# 5_Airframe-NXP_i_MX7_Power.net
KiCad netlist of a schematic drawn in Altium Designer
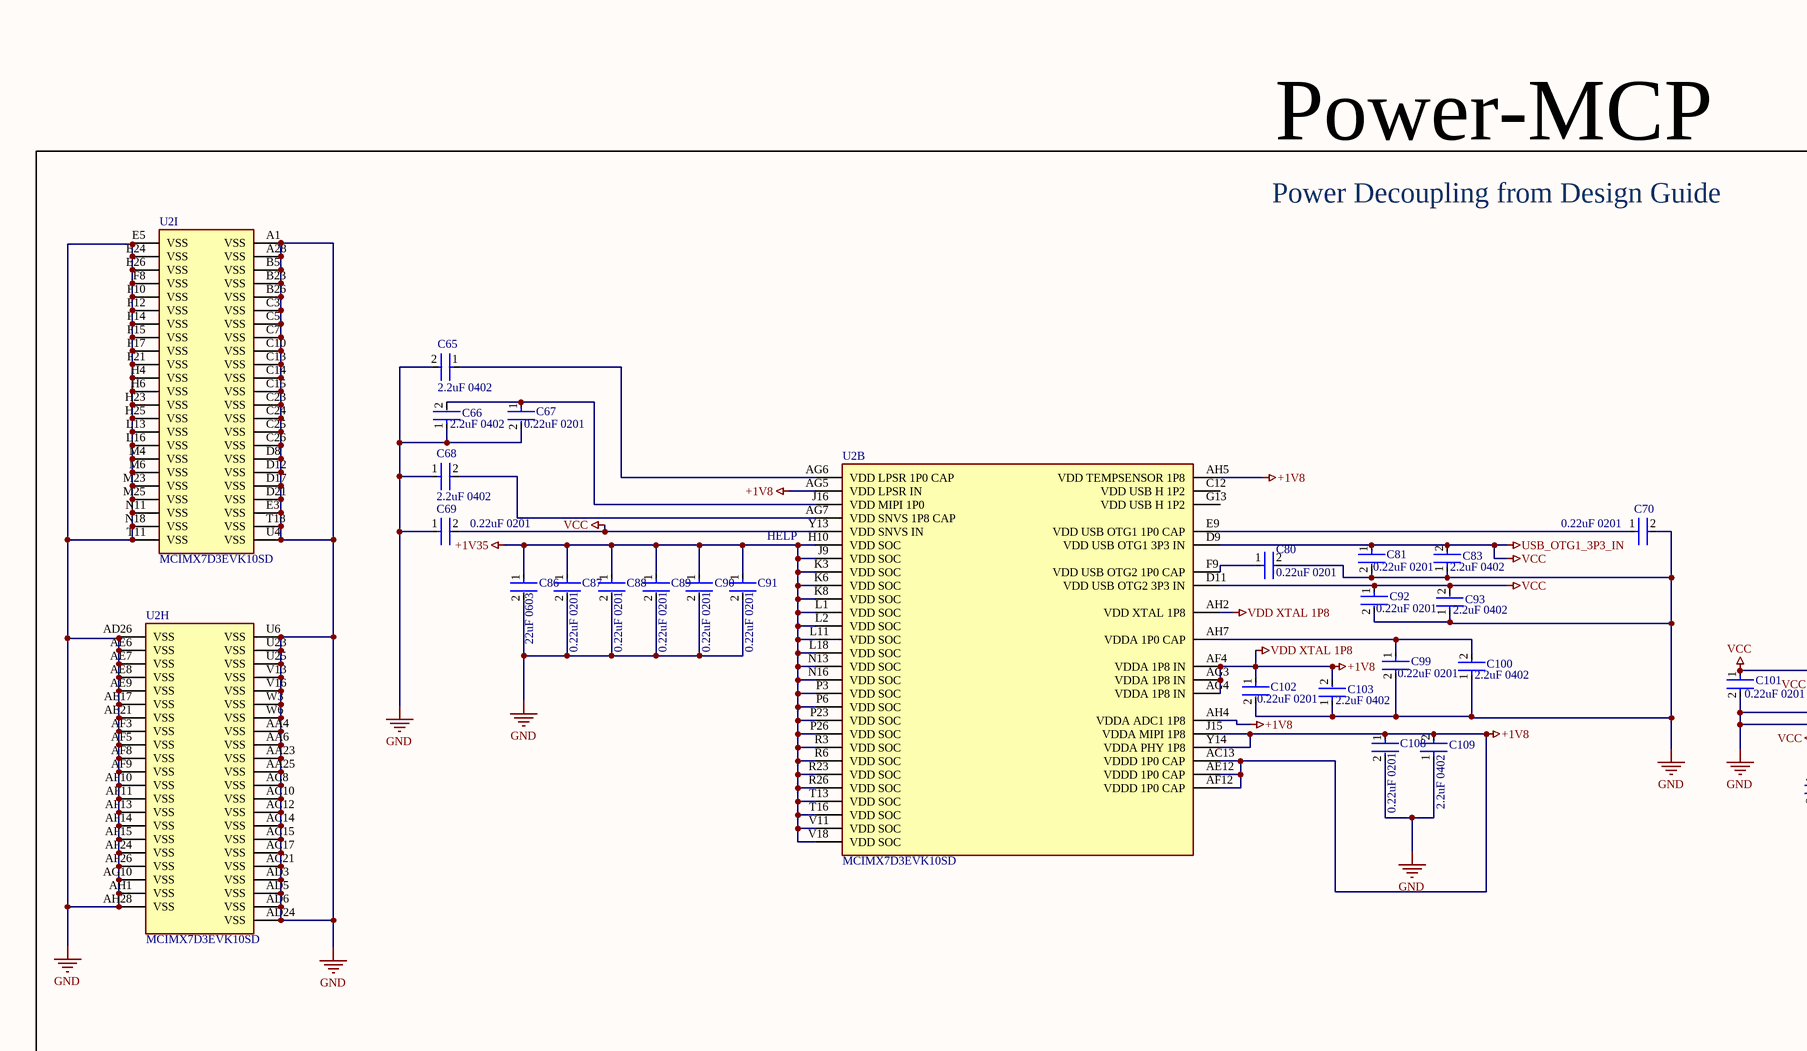
[diagram p0: 5_Airframe-NXP_i.MX7_Power.SchDoc, left]
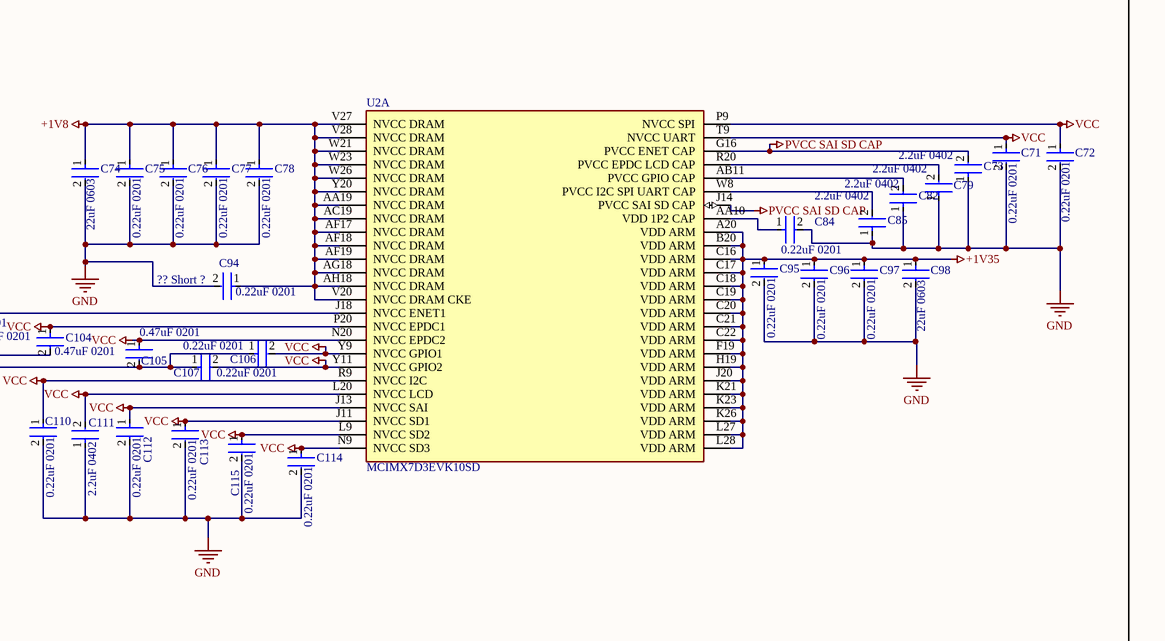
[diagram p1: 5_Airframe-NXP_i.MX7_Power.SchDoc, right]

(export (version "E")
  (design (tool "Eeschema 10.0.6"))
  (components
    (comp (ref "C65")
      (value "2.2uF 0402")
      (footprint "FP-C0402C225M9PACTU-MFG")
      (description "CAP CER 2.2UF 6.3V X5R 0402")
      (fields (field (name "VOLTAGE") "6.3V") (field (name "TOLERANCE") "20%"))
      (libsource (lib "Altium Content Vault") (part "b4654b650e69147ec39a6b967a45e02"))
    )
    (comp (ref "C66")
      (value "2.2uF 0402")
      (footprint "FP-C0402C225M9PACTU-MFG")
      (description "CAP CER 2.2UF 6.3V X5R 0402")
      (fields (field (name "VOLTAGE") "6.3V") (field (name "TOLERANCE") "20%"))
      (libsource (lib "Altium Content Vault") (part "b4654b650e69147ec39a6b967a45e02"))
    )
    (comp (ref "C67")
      (value "0.22uF 0201")
      (footprint "FP-C0603-030-0_03-IPC_C")
      (description "Multilayer Ceramic Capacitors 220nF ±10% 6.3V X6S SMD 0201")
      (fields (field (name "TOLERANCE") "10%"))
      (libsource (lib "Altium Content Vault") (part "02cd4be3c70576c341d710602a673aa"))
    )
    (comp (ref "C68")
      (value "2.2uF 0402")
      (footprint "FP-C0402C225M9PACTU-MFG")
      (description "CAP CER 2.2UF 6.3V X5R 0402")
      (fields (field (name "VOLTAGE") "6.3V") (field (name "TOLERANCE") "20%"))
      (libsource (lib "Altium Content Vault") (part "b4654b650e69147ec39a6b967a45e02"))
    )
    (comp (ref "C69")
      (value "0.22uF 0201")
      (footprint "FP-C0603-030-0_03-IPC_C")
      (description "Multilayer Ceramic Capacitors 220nF ±10% 6.3V X6S SMD 0201")
      (fields (field (name "TOLERANCE") "10%"))
      (libsource (lib "Altium Content Vault") (part "02cd4be3c70576c341d710602a673aa"))
    )
    (comp (ref "C70")
      (value "0.22uF 0201")
      (footprint "FP-C0603-030-0_03-IPC_C")
      (description "Multilayer Ceramic Capacitors 220nF ±10% 6.3V X6S SMD 0201")
      (fields (field (name "TOLERANCE") "10%"))
      (libsource (lib "Altium Content Vault") (part "02cd4be3c70576c341d710602a673aa"))
    )
    (comp (ref "C71")
      (value "0.22uF 0201")
      (footprint "FP-C0603-030-0_03-IPC_C")
      (description "Multilayer Ceramic Capacitors 220nF ±10% 6.3V X6S SMD 0201")
      (fields (field (name "TOLERANCE") "10%"))
      (libsource (lib "Altium Content Vault") (part "02cd4be3c70576c341d710602a673aa"))
    )
    (comp (ref "C72")
      (value "0.22uF 0201")
      (footprint "FP-C0603-030-0_03-IPC_C")
      (description "Multilayer Ceramic Capacitors 220nF ±10% 6.3V X6S SMD 0201")
      (fields (field (name "TOLERANCE") "10%"))
      (libsource (lib "Altium Content Vault") (part "02cd4be3c70576c341d710602a673aa"))
    )
    (comp (ref "C73")
      (value "2.2uF 0402")
      (footprint "FP-C0402C225M9PACTU-MFG")
      (description "CAP CER 2.2UF 6.3V X5R 0402")
      (fields (field (name "VOLTAGE") "6.3V") (field (name "TOLERANCE") "20%"))
      (libsource (lib "Altium Content Vault") (part "b4654b650e69147ec39a6b967a45e02"))
    )
    (comp (ref "C74")
      (value "22uF 0603")
      (footprint "FP-GRM188-0_2-IPC_C")
      (description "Chip Multilayer Ceramic Capacitors for General Purpose, 0603, 22uF, X5R, 15%, 20%, 10V")
      (fields (field (name "TOLERANCE") "20%"))
      (libsource (lib "Altium Content Vault") (part "11868f565c42a9108669ba33697ecf6"))
    )
    (comp (ref "C75")
      (value "0.22uF 0201")
      (footprint "FP-C0603-030-0_03-IPC_C")
      (description "Multilayer Ceramic Capacitors 220nF ±10% 6.3V X6S SMD 0201")
      (fields (field (name "TOLERANCE") "10%"))
      (libsource (lib "Altium Content Vault") (part "02cd4be3c70576c341d710602a673aa"))
    )
    (comp (ref "C76")
      (value "0.22uF 0201")
      (footprint "FP-C0603-030-0_03-IPC_C")
      (description "Multilayer Ceramic Capacitors 220nF ±10% 6.3V X6S SMD 0201")
      (fields (field (name "TOLERANCE") "10%"))
      (libsource (lib "Altium Content Vault") (part "02cd4be3c70576c341d710602a673aa"))
    )
    (comp (ref "C77")
      (value "0.22uF 0201")
      (footprint "FP-C0603-030-0_03-IPC_C")
      (description "Multilayer Ceramic Capacitors 220nF ±10% 6.3V X6S SMD 0201")
      (fields (field (name "TOLERANCE") "10%"))
      (libsource (lib "Altium Content Vault") (part "02cd4be3c70576c341d710602a673aa"))
    )
    (comp (ref "C78")
      (value "0.22uF 0201")
      (footprint "FP-C0603-030-0_03-IPC_C")
      (description "Multilayer Ceramic Capacitors 220nF ±10% 6.3V X6S SMD 0201")
      (fields (field (name "TOLERANCE") "10%"))
      (libsource (lib "Altium Content Vault") (part "02cd4be3c70576c341d710602a673aa"))
    )
    (comp (ref "C79")
      (value "2.2uF 0402")
      (footprint "FP-C0402C225M9PACTU-MFG")
      (description "CAP CER 2.2UF 6.3V X5R 0402")
      (fields (field (name "VOLTAGE") "6.3V") (field (name "TOLERANCE") "20%"))
      (libsource (lib "Altium Content Vault") (part "b4654b650e69147ec39a6b967a45e02"))
    )
    (comp (ref "C80")
      (value "0.22uF 0201")
      (footprint "FP-C0603-030-0_03-IPC_C")
      (description "Multilayer Ceramic Capacitors 220nF ±10% 6.3V X6S SMD 0201")
      (fields (field (name "TOLERANCE") "10%"))
      (libsource (lib "Altium Content Vault") (part "02cd4be3c70576c341d710602a673aa"))
    )
    (comp (ref "C81")
      (value "0.22uF 0201")
      (footprint "FP-C0603-030-0_03-IPC_C")
      (description "Multilayer Ceramic Capacitors 220nF ±10% 6.3V X6S SMD 0201")
      (fields (field (name "TOLERANCE") "10%"))
      (libsource (lib "Altium Content Vault") (part "02cd4be3c70576c341d710602a673aa"))
    )
    (comp (ref "C82")
      (value "2.2uF 0402")
      (footprint "FP-C0402C225M9PACTU-MFG")
      (description "CAP CER 2.2UF 6.3V X5R 0402")
      (fields (field (name "VOLTAGE") "6.3V") (field (name "TOLERANCE") "20%"))
      (libsource (lib "Altium Content Vault") (part "b4654b650e69147ec39a6b967a45e02"))
    )
    (comp (ref "C83")
      (value "2.2uF 0402")
      (footprint "FP-C0402C225M9PACTU-MFG")
      (description "CAP CER 2.2UF 6.3V X5R 0402")
      (fields (field (name "VOLTAGE") "6.3V") (field (name "TOLERANCE") "20%"))
      (libsource (lib "Altium Content Vault") (part "b4654b650e69147ec39a6b967a45e02"))
    )
    (comp (ref "C84")
      (value "0.22uF 0201")
      (footprint "FP-C0603-030-0_03-IPC_C")
      (description "Multilayer Ceramic Capacitors 220nF ±10% 6.3V X6S SMD 0201")
      (fields (field (name "TOLERANCE") "10%"))
      (libsource (lib "Altium Content Vault") (part "02cd4be3c70576c341d710602a673aa"))
    )
    (comp (ref "C85")
      (value "2.2uF 0402")
      (footprint "FP-C0402C225M9PACTU-MFG")
      (description "CAP CER 2.2UF 6.3V X5R 0402")
      (fields (field (name "VOLTAGE") "6.3V") (field (name "TOLERANCE") "20%"))
      (libsource (lib "Altium Content Vault") (part "b4654b650e69147ec39a6b967a45e02"))
    )
    (comp (ref "C86")
      (value "22uF 0603")
      (footprint "FP-GRM188-0_2-IPC_C")
      (description "Chip Multilayer Ceramic Capacitors for General Purpose, 0603, 22uF, X5R, 15%, 20%, 10V")
      (fields (field (name "TOLERANCE") "20%"))
      (libsource (lib "Altium Content Vault") (part "11868f565c42a9108669ba33697ecf6"))
    )
    (comp (ref "C87")
      (value "0.22uF 0201")
      (footprint "FP-C0603-030-0_03-IPC_C")
      (description "Multilayer Ceramic Capacitors 220nF ±10% 6.3V X6S SMD 0201")
      (fields (field (name "TOLERANCE") "10%"))
      (libsource (lib "Altium Content Vault") (part "02cd4be3c70576c341d710602a673aa"))
    )
    (comp (ref "C88")
      (value "0.22uF 0201")
      (footprint "FP-C0603-030-0_03-IPC_C")
      (description "Multilayer Ceramic Capacitors 220nF ±10% 6.3V X6S SMD 0201")
      (fields (field (name "TOLERANCE") "10%"))
      (libsource (lib "Altium Content Vault") (part "02cd4be3c70576c341d710602a673aa"))
    )
    (comp (ref "C89")
      (value "0.22uF 0201")
      (footprint "FP-C0603-030-0_03-IPC_C")
      (description "Multilayer Ceramic Capacitors 220nF ±10% 6.3V X6S SMD 0201")
      (fields (field (name "TOLERANCE") "10%"))
      (libsource (lib "Altium Content Vault") (part "02cd4be3c70576c341d710602a673aa"))
    )
    (comp (ref "C90")
      (value "0.22uF 0201")
      (footprint "FP-C0603-030-0_03-IPC_C")
      (description "Multilayer Ceramic Capacitors 220nF ±10% 6.3V X6S SMD 0201")
      (fields (field (name "TOLERANCE") "10%"))
      (libsource (lib "Altium Content Vault") (part "02cd4be3c70576c341d710602a673aa"))
    )
    (comp (ref "C91")
      (value "0.22uF 0201")
      (footprint "FP-C0603-030-0_03-IPC_C")
      (description "Multilayer Ceramic Capacitors 220nF ±10% 6.3V X6S SMD 0201")
      (fields (field (name "TOLERANCE") "10%"))
      (libsource (lib "Altium Content Vault") (part "02cd4be3c70576c341d710602a673aa"))
    )
    (comp (ref "C92")
      (value "0.22uF 0201")
      (footprint "FP-C0603-030-0_03-IPC_C")
      (description "Multilayer Ceramic Capacitors 220nF ±10% 6.3V X6S SMD 0201")
      (fields (field (name "TOLERANCE") "10%"))
      (libsource (lib "Altium Content Vault") (part "02cd4be3c70576c341d710602a673aa"))
    )
    (comp (ref "C93")
      (value "2.2uF 0402")
      (footprint "FP-C0402C225M9PACTU-MFG")
      (description "CAP CER 2.2UF 6.3V X5R 0402")
      (fields (field (name "VOLTAGE") "6.3V") (field (name "TOLERANCE") "20%"))
      (libsource (lib "Altium Content Vault") (part "b4654b650e69147ec39a6b967a45e02"))
    )
    (comp (ref "C94")
      (value "0.22uF 0201")
      (footprint "FP-C0603-030-0_03-IPC_C")
      (description "Multilayer Ceramic Capacitors 220nF ±10% 6.3V X6S SMD 0201")
      (fields (field (name "TOLERANCE") "10%"))
      (libsource (lib "Altium Content Vault") (part "02cd4be3c70576c341d710602a673aa"))
    )
    (comp (ref "C95")
      (value "0.22uF 0201")
      (footprint "FP-C0603-030-0_03-IPC_C")
      (description "Multilayer Ceramic Capacitors 220nF ±10% 6.3V X6S SMD 0201")
      (fields (field (name "TOLERANCE") "10%"))
      (libsource (lib "Altium Content Vault") (part "02cd4be3c70576c341d710602a673aa"))
    )
    (comp (ref "C96")
      (value "0.22uF 0201")
      (footprint "FP-C0603-030-0_03-IPC_C")
      (description "Multilayer Ceramic Capacitors 220nF ±10% 6.3V X6S SMD 0201")
      (fields (field (name "TOLERANCE") "10%"))
      (libsource (lib "Altium Content Vault") (part "02cd4be3c70576c341d710602a673aa"))
    )
    (comp (ref "C97")
      (value "0.22uF 0201")
      (footprint "FP-C0603-030-0_03-IPC_C")
      (description "Multilayer Ceramic Capacitors 220nF ±10% 6.3V X6S SMD 0201")
      (fields (field (name "TOLERANCE") "10%"))
      (libsource (lib "Altium Content Vault") (part "02cd4be3c70576c341d710602a673aa"))
    )
    (comp (ref "C98")
      (value "22uF 0603")
      (footprint "FP-GRM188-0_2-IPC_C")
      (description "Chip Multilayer Ceramic Capacitors for General Purpose, 0603, 22uF, X5R, 15%, 20%, 10V")
      (fields (field (name "TOLERANCE") "20%"))
      (libsource (lib "Altium Content Vault") (part "11868f565c42a9108669ba33697ecf6"))
    )
    (comp (ref "C99")
      (value "0.22uF 0201")
      (footprint "FP-C0603-030-0_03-IPC_C")
      (description "Multilayer Ceramic Capacitors 220nF ±10% 6.3V X6S SMD 0201")
      (fields (field (name "TOLERANCE") "10%"))
      (libsource (lib "Altium Content Vault") (part "02cd4be3c70576c341d710602a673aa"))
    )
    (comp (ref "C100")
      (value "2.2uF 0402")
      (footprint "FP-C0402C225M9PACTU-MFG")
      (description "CAP CER 2.2UF 6.3V X5R 0402")
      (fields (field (name "VOLTAGE") "6.3V") (field (name "TOLERANCE") "20%"))
      (libsource (lib "Altium Content Vault") (part "b4654b650e69147ec39a6b967a45e02"))
    )
    (comp (ref "C101")
      (value "0.22uF 0201")
      (footprint "FP-C0603-030-0_03-IPC_C")
      (description "Multilayer Ceramic Capacitors 220nF ±10% 6.3V X6S SMD 0201")
      (fields (field (name "TOLERANCE") "10%"))
      (libsource (lib "Altium Content Vault") (part "02cd4be3c70576c341d710602a673aa"))
    )
    (comp (ref "C102")
      (value "0.22uF 0201")
      (footprint "FP-C0603-030-0_03-IPC_C")
      (description "Multilayer Ceramic Capacitors 220nF ±10% 6.3V X6S SMD 0201")
      (fields (field (name "TOLERANCE") "10%"))
      (libsource (lib "Altium Content Vault") (part "02cd4be3c70576c341d710602a673aa"))
    )
    (comp (ref "C103")
      (value "2.2uF 0402")
      (footprint "FP-C0402C225M9PACTU-MFG")
      (description "CAP CER 2.2UF 6.3V X5R 0402")
      (fields (field (name "VOLTAGE") "6.3V") (field (name "TOLERANCE") "20%"))
      (libsource (lib "Altium Content Vault") (part "b4654b650e69147ec39a6b967a45e02"))
    )
    (comp (ref "C104")
      (value "0.47uF 0201")
      (footprint "FP-C0603-030-0_03-IPC_C")
      (description "Multilayer Ceramic Capacitors 220nF ±10% 6.3V X6S SMD 0201")
      (fields (field (name "TOLERANCE") "10%"))
      (libsource (lib "Altium Content Vault") (part "02cd4be3c70576c341d710602a673aa"))
    )
    (comp (ref "C105")
      (value "0.47uF 0201")
      (footprint "FP-C0603-030-0_03-IPC_C")
      (description "Multilayer Ceramic Capacitors 220nF ±10% 6.3V X6S SMD 0201")
      (fields (field (name "TOLERANCE") "10%"))
      (libsource (lib "Altium Content Vault") (part "02cd4be3c70576c341d710602a673aa"))
    )
    (comp (ref "C106")
      (value "0.22uF 0201")
      (footprint "FP-C0603-030-0_03-IPC_C")
      (description "Multilayer Ceramic Capacitors 220nF ±10% 6.3V X6S SMD 0201")
      (fields (field (name "TOLERANCE") "10%"))
      (libsource (lib "Altium Content Vault") (part "02cd4be3c70576c341d710602a673aa"))
    )
    (comp (ref "C107")
      (value "0.22uF 0201")
      (footprint "FP-C0603-030-0_03-IPC_C")
      (description "Multilayer Ceramic Capacitors 220nF ±10% 6.3V X6S SMD 0201")
      (fields (field (name "TOLERANCE") "10%"))
      (libsource (lib "Altium Content Vault") (part "02cd4be3c70576c341d710602a673aa"))
    )
    (comp (ref "C108")
      (value "0.22uF 0201")
      (footprint "FP-C0603-030-0_03-IPC_C")
      (description "Multilayer Ceramic Capacitors 220nF ±10% 6.3V X6S SMD 0201")
      (fields (field (name "TOLERANCE") "10%"))
      (libsource (lib "Altium Content Vault") (part "02cd4be3c70576c341d710602a673aa"))
    )
    (comp (ref "C109")
      (value "2.2uF 0402")
      (footprint "FP-C0402C225M9PACTU-MFG")
      (description "CAP CER 2.2UF 6.3V X5R 0402")
      (fields (field (name "VOLTAGE") "6.3V") (field (name "TOLERANCE") "20%"))
      (libsource (lib "Altium Content Vault") (part "b4654b650e69147ec39a6b967a45e02"))
    )
    (comp (ref "C110")
      (value "0.22uF 0201")
      (footprint "FP-C0603-030-0_03-IPC_C")
      (description "Multilayer Ceramic Capacitors 220nF ±10% 6.3V X6S SMD 0201")
      (fields (field (name "TOLERANCE") "10%"))
      (libsource (lib "Altium Content Vault") (part "02cd4be3c70576c341d710602a673aa"))
    )
    (comp (ref "C111")
      (value "2.2uF 0402")
      (footprint "FP-C0402C225M9PACTU-MFG")
      (description "CAP CER 2.2UF 6.3V X5R 0402")
      (fields (field (name "VOLTAGE") "6.3V") (field (name "TOLERANCE") "20%"))
      (libsource (lib "Altium Content Vault") (part "b4654b650e69147ec39a6b967a45e02"))
    )
    (comp (ref "C112")
      (value "0.22uF 0201")
      (footprint "FP-C0603-030-0_03-IPC_C")
      (description "Multilayer Ceramic Capacitors 220nF ±10% 6.3V X6S SMD 0201")
      (fields (field (name "TOLERANCE") "10%"))
      (libsource (lib "Altium Content Vault") (part "02cd4be3c70576c341d710602a673aa"))
    )
    (comp (ref "C113")
      (value "0.22uF 0201")
      (footprint "FP-C0603-030-0_03-IPC_C")
      (description "Multilayer Ceramic Capacitors 220nF ±10% 6.3V X6S SMD 0201")
      (fields (field (name "TOLERANCE") "10%"))
      (libsource (lib "Altium Content Vault") (part "02cd4be3c70576c341d710602a673aa"))
    )
    (comp (ref "C114")
      (value "0.22uF 0201")
      (footprint "FP-C0603-030-0_03-IPC_C")
      (description "Multilayer Ceramic Capacitors 220nF ±10% 6.3V X6S SMD 0201")
      (fields (field (name "TOLERANCE") "10%"))
      (libsource (lib "Altium Content Vault") (part "02cd4be3c70576c341d710602a673aa"))
    )
    (comp (ref "C115")
      (value "0.22uF 0201")
      (footprint "FP-C0603-030-0_03-IPC_C")
      (description "Multilayer Ceramic Capacitors 220nF ±10% 6.3V X6S SMD 0201")
      (fields (field (name "TOLERANCE") "10%"))
      (libsource (lib "Altium Content Vault") (part "02cd4be3c70576c341d710602a673aa"))
    )
    (comp (ref "U2")
      (value "MCIMX7D3EVK10SD")
      (footprint "FP-SOT1839-1-IPC_C")
      (description "I.MX 7DUAL: REV 1.3")
      (fields
        (field (name "MANUFACTURER") "NXP")
        (field (name "OCTOPART") "https://octopart.com/mcimx7d3evk10sd-nxp+semiconductors-84356608")
      )
      (libsource (lib "Altium Content Vault") (part "158777adc505239d6b0373594f9eb19"))
    )
  )
  (nets
    (net (code "1") (name "+1V8") (class "Default")
      (node (ref "C102") (pin "1") (pinfunction "1_1") (pintype "passive"))
      (node (ref "C103") (pin "2") (pinfunction "2_2") (pintype "passive"))
      (node (ref "C108") (pin "1") (pinfunction "1_1") (pintype "passive"))
      (node (ref "C109") (pin "2") (pinfunction "2_2") (pintype "passive"))
      (node (ref "C74") (pin "1") (pinfunction "1_1") (pintype "passive"))
      (node (ref "C75") (pin "1") (pinfunction "1_1") (pintype "passive"))
      (node (ref "C76") (pin "1") (pinfunction "1_1") (pintype "passive"))
      (node (ref "C77") (pin "1") (pinfunction "1_1") (pintype "passive"))
      (node (ref "C78") (pin "1") (pinfunction "1_1") (pintype "passive"))
      (node (ref "C94") (pin "1") (pinfunction "1_1") (pintype "passive"))
      (node (ref "U2") (pin "AA19") (pinfunction "NVCC_DRAM_AA19") (pintype "power_in"))
      (node (ref "U2") (pin "AC13") (pinfunction "VDDD_1P0_CAP_AC13") (pintype "power_in"))
      (node (ref "U2") (pin "AC19") (pinfunction "NVCC_DRAM_AC19") (pintype "power_in"))
      (node (ref "U2") (pin "AE12") (pinfunction "VDDD_1P0_CAP_AE12") (pintype "power_in"))
      (node (ref "U2") (pin "AF12") (pinfunction "VDDD_1P0_CAP_AF12") (pintype "power_in"))
      (node (ref "U2") (pin "AF17") (pinfunction "NVCC_DRAM_AF17") (pintype "power_in"))
      (node (ref "U2") (pin "AF18") (pinfunction "NVCC_DRAM_AF18") (pintype "power_in"))
      (node (ref "U2") (pin "AF19") (pinfunction "NVCC_DRAM_AF19") (pintype "power_in"))
      (node (ref "U2") (pin "AF4") (pinfunction "VDDA_1P8_IN_AF4") (pintype "power_in"))
      (node (ref "U2") (pin "AG18") (pinfunction "NVCC_DRAM_AG18") (pintype "power_in"))
      (node (ref "U2") (pin "AG3") (pinfunction "VDDA_1P8_IN_AG3") (pintype "power_in"))
      (node (ref "U2") (pin "AG4") (pinfunction "VDDA_1P8_IN_AG4") (pintype "power_in"))
      (node (ref "U2") (pin "AG5") (pinfunction "VDD_LPSR_IN_AG5") (pintype "power_in"))
      (node (ref "U2") (pin "AH18") (pinfunction "NVCC_DRAM_AH18") (pintype "power_in"))
      (node (ref "U2") (pin "AH2") (pinfunction "VDD_XTAL_1P8_AH2") (pintype "power_in"))
      (node (ref "U2") (pin "AH4") (pinfunction "VDDA_ADC1_1P8_AH4") (pintype "power_in"))
      (node (ref "U2") (pin "AH5") (pinfunction "VDD_TEMPSENSOR_1P8_AH5") (pintype "power_in"))
      (node (ref "U2") (pin "J15") (pinfunction "VDDA_MIPI_1P8_J15") (pintype "power_in"))
      (node (ref "U2") (pin "V20") (pinfunction "NVCC_DRAM_CKE_V20") (pintype "power_in"))
      (node (ref "U2") (pin "V27") (pinfunction "NVCC_DRAM_V27") (pintype "power_in"))
      (node (ref "U2") (pin "V28") (pinfunction "NVCC_DRAM_V28") (pintype "power_in"))
      (node (ref "U2") (pin "W21") (pinfunction "NVCC_DRAM_W21") (pintype "power_in"))
      (node (ref "U2") (pin "W23") (pinfunction "NVCC_DRAM_W23") (pintype "power_in"))
      (node (ref "U2") (pin "W26") (pinfunction "NVCC_DRAM_W26") (pintype "power_in"))
      (node (ref "U2") (pin "Y14") (pinfunction "VDDA_PHY_1P8_Y14") (pintype "power_in"))
      (node (ref "U2") (pin "Y20") (pinfunction "NVCC_DRAM_Y20") (pintype "power_in"))
    )
    (net (code "2") (name "+1V35") (class "Default")
      (node (ref "C86") (pin "1") (pinfunction "1_1") (pintype "passive"))
      (node (ref "C87") (pin "1") (pinfunction "1_1") (pintype "passive"))
      (node (ref "C88") (pin "1") (pinfunction "1_1") (pintype "passive"))
      (node (ref "C89") (pin "1") (pinfunction "1_1") (pintype "passive"))
      (node (ref "C90") (pin "1") (pinfunction "1_1") (pintype "passive"))
      (node (ref "C91") (pin "1") (pinfunction "1_1") (pintype "passive"))
      (node (ref "C95") (pin "1") (pinfunction "1_1") (pintype "passive"))
      (node (ref "C96") (pin "1") (pinfunction "1_1") (pintype "passive"))
      (node (ref "C97") (pin "1") (pinfunction "1_1") (pintype "passive"))
      (node (ref "C98") (pin "1") (pinfunction "1_1") (pintype "passive"))
      (node (ref "U2") (pin "A20") (pinfunction "VDD_ARM_A20") (pintype "power_in"))
      (node (ref "U2") (pin "B20") (pinfunction "VDD_ARM_B20") (pintype "power_in"))
      (node (ref "U2") (pin "C16") (pinfunction "VDD_ARM_C16") (pintype "power_in"))
      (node (ref "U2") (pin "C17") (pinfunction "VDD_ARM_C17") (pintype "power_in"))
      (node (ref "U2") (pin "C18") (pinfunction "VDD_ARM_C18") (pintype "power_in"))
      (node (ref "U2") (pin "C19") (pinfunction "VDD_ARM_C19") (pintype "power_in"))
      (node (ref "U2") (pin "C20") (pinfunction "VDD_ARM_C20") (pintype "power_in"))
      (node (ref "U2") (pin "C21") (pinfunction "VDD_ARM_C21") (pintype "power_in"))
      (node (ref "U2") (pin "C22") (pinfunction "VDD_ARM_C22") (pintype "power_in"))
      (node (ref "U2") (pin "F19") (pinfunction "VDD_ARM_F19") (pintype "power_in"))
      (node (ref "U2") (pin "H10") (pinfunction "VDD_SOC_H10") (pintype "power_in"))
      (node (ref "U2") (pin "H19") (pinfunction "VDD_ARM_H19") (pintype "power_in"))
      (node (ref "U2") (pin "J20") (pinfunction "VDD_ARM_J20") (pintype "power_in"))
      (node (ref "U2") (pin "J9") (pinfunction "VDD_SOC_J9") (pintype "power_in"))
      (node (ref "U2") (pin "K21") (pinfunction "VDD_ARM_K21") (pintype "power_in"))
      (node (ref "U2") (pin "K23") (pinfunction "VDD_ARM_K23") (pintype "power_in"))
      (node (ref "U2") (pin "K26") (pinfunction "VDD_ARM_K26") (pintype "power_in"))
      (node (ref "U2") (pin "K3") (pinfunction "VDD_SOC_K3") (pintype "power_in"))
      (node (ref "U2") (pin "K6") (pinfunction "VDD_SOC_K6") (pintype "power_in"))
      (node (ref "U2") (pin "K8") (pinfunction "VDD_SOC_K8") (pintype "power_in"))
      (node (ref "U2") (pin "L1") (pinfunction "VDD_SOC_L1") (pintype "power_in"))
      (node (ref "U2") (pin "L11") (pinfunction "VDD_SOC_L11") (pintype "power_in"))
      (node (ref "U2") (pin "L18") (pinfunction "VDD_SOC_L18") (pintype "power_in"))
      (node (ref "U2") (pin "L2") (pinfunction "VDD_SOC_L2") (pintype "power_in"))
      (node (ref "U2") (pin "L27") (pinfunction "VDD_ARM_L27") (pintype "power_in"))
      (node (ref "U2") (pin "L28") (pinfunction "VDD_ARM_L28") (pintype "power_in"))
      (node (ref "U2") (pin "N13") (pinfunction "VDD_SOC_N13") (pintype "power_in"))
      (node (ref "U2") (pin "N16") (pinfunction "VDD_SOC_N16") (pintype "power_in"))
      (node (ref "U2") (pin "P23") (pinfunction "VDD_SOC_P23") (pintype "power_in"))
      (node (ref "U2") (pin "P26") (pinfunction "VDD_SOC_P26") (pintype "power_in"))
      (node (ref "U2") (pin "P3") (pinfunction "VDD_SOC_P3") (pintype "power_in"))
      (node (ref "U2") (pin "P6") (pinfunction "VDD_SOC_P6") (pintype "power_in"))
      (node (ref "U2") (pin "R23") (pinfunction "VDD_SOC_R23") (pintype "power_in"))
      (node (ref "U2") (pin "R26") (pinfunction "VDD_SOC_R26") (pintype "power_in"))
      (node (ref "U2") (pin "R3") (pinfunction "VDD_SOC_R3") (pintype "power_in"))
      (node (ref "U2") (pin "R6") (pinfunction "VDD_SOC_R6") (pintype "power_in"))
      (node (ref "U2") (pin "T13") (pinfunction "VDD_SOC_T13") (pintype "power_in"))
      (node (ref "U2") (pin "T16") (pinfunction "VDD_SOC_T16") (pintype "power_in"))
      (node (ref "U2") (pin "V11") (pinfunction "VDD_SOC_V11") (pintype "power_in"))
      (node (ref "U2") (pin "V18") (pinfunction "VDD_SOC_V18") (pintype "power_in"))
    )
    (net (code "3") (name "GND") (class "Default")
      (node (ref "C100") (pin "1") (pinfunction "1_1") (pintype "passive"))
      (node (ref "C101") (pin "2") (pinfunction "2_2") (pintype "passive"))
      (node (ref "C102") (pin "2") (pinfunction "2_2") (pintype "passive"))
      (node (ref "C103") (pin "1") (pinfunction "1_1") (pintype "passive"))
      (node (ref "C104") (pin "2") (pinfunction "2_2") (pintype "passive"))
      (node (ref "C105") (pin "2") (pinfunction "2_2") (pintype "passive"))
      (node (ref "C106") (pin "1") (pinfunction "1_1") (pintype "passive"))
      (node (ref "C107") (pin "1") (pinfunction "1_1") (pintype "passive"))
      (node (ref "C108") (pin "2") (pinfunction "2_2") (pintype "passive"))
      (node (ref "C109") (pin "1") (pinfunction "1_1") (pintype "passive"))
      (node (ref "C110") (pin "2") (pinfunction "2_2") (pintype "passive"))
      (node (ref "C111") (pin "1") (pinfunction "1_1") (pintype "passive"))
      (node (ref "C112") (pin "2") (pinfunction "2_2") (pintype "passive"))
      (node (ref "C113") (pin "2") (pinfunction "2_2") (pintype "passive"))
      (node (ref "C114") (pin "2") (pinfunction "2_2") (pintype "passive"))
      (node (ref "C115") (pin "2") (pinfunction "2_2") (pintype "passive"))
      (node (ref "C65") (pin "2") (pinfunction "2_2") (pintype "passive"))
      (node (ref "C66") (pin "1") (pinfunction "1_1") (pintype "passive"))
      (node (ref "C67") (pin "2") (pinfunction "2_2") (pintype "passive"))
      (node (ref "C68") (pin "1") (pinfunction "1_1") (pintype "passive"))
      (node (ref "C69") (pin "1") (pinfunction "1_1") (pintype "passive"))
      (node (ref "C70") (pin "2") (pinfunction "2_2") (pintype "passive"))
      (node (ref "C71") (pin "2") (pinfunction "2_2") (pintype "passive"))
      (node (ref "C72") (pin "2") (pinfunction "2_2") (pintype "passive"))
      (node (ref "C73") (pin "1") (pinfunction "1_1") (pintype "passive"))
      (node (ref "C74") (pin "2") (pinfunction "2_2") (pintype "passive"))
      (node (ref "C75") (pin "2") (pinfunction "2_2") (pintype "passive"))
      (node (ref "C76") (pin "2") (pinfunction "2_2") (pintype "passive"))
      (node (ref "C77") (pin "2") (pinfunction "2_2") (pintype "passive"))
      (node (ref "C78") (pin "2") (pinfunction "2_2") (pintype "passive"))
      (node (ref "C79") (pin "1") (pinfunction "1_1") (pintype "passive"))
      (node (ref "C80") (pin "2") (pinfunction "2_2") (pintype "passive"))
      (node (ref "C81") (pin "2") (pinfunction "2_2") (pintype "passive"))
      (node (ref "C82") (pin "1") (pinfunction "1_1") (pintype "passive"))
      (node (ref "C83") (pin "1") (pinfunction "1_1") (pintype "passive"))
      (node (ref "C84") (pin "2") (pinfunction "2_2") (pintype "passive"))
      (node (ref "C85") (pin "1") (pinfunction "1_1") (pintype "passive"))
      (node (ref "C86") (pin "2") (pinfunction "2_2") (pintype "passive"))
      (node (ref "C87") (pin "2") (pinfunction "2_2") (pintype "passive"))
      (node (ref "C88") (pin "2") (pinfunction "2_2") (pintype "passive"))
      (node (ref "C89") (pin "2") (pinfunction "2_2") (pintype "passive"))
      (node (ref "C90") (pin "2") (pinfunction "2_2") (pintype "passive"))
      (node (ref "C91") (pin "2") (pinfunction "2_2") (pintype "passive"))
      (node (ref "C92") (pin "2") (pinfunction "2_2") (pintype "passive"))
      (node (ref "C93") (pin "1") (pinfunction "1_1") (pintype "passive"))
      (node (ref "C94") (pin "2") (pinfunction "2_2") (pintype "passive"))
      (node (ref "C95") (pin "2") (pinfunction "2_2") (pintype "passive"))
      (node (ref "C96") (pin "2") (pinfunction "2_2") (pintype "passive"))
      (node (ref "C97") (pin "2") (pinfunction "2_2") (pintype "passive"))
      (node (ref "C98") (pin "2") (pinfunction "2_2") (pintype "passive"))
      (node (ref "C99") (pin "2") (pinfunction "2_2") (pintype "passive"))
      (node (ref "U2") (pin "A1") (pinfunction "VSS_A1") (pintype "power_in"))
      (node (ref "U2") (pin "A28") (pinfunction "VSS_A28") (pintype "power_in"))
      (node (ref "U2") (pin "AA23") (pinfunction "VSS_AA23") (pintype "power_in"))
      (node (ref "U2") (pin "AA25") (pinfunction "VSS_AA25") (pintype "power_in"))
      (node (ref "U2") (pin "AA4") (pinfunction "VSS_AA4") (pintype "power_in"))
      (node (ref "U2") (pin "AA6") (pinfunction "VSS_AA6") (pintype "power_in"))
      (node (ref "U2") (pin "AC10") (pinfunction "VSS_AC10") (pintype "power_in"))
      (node (ref "U2") (pin "AC12") (pinfunction "VSS_AC12") (pintype "power_in"))
      (node (ref "U2") (pin "AC14") (pinfunction "VSS_AC14") (pintype "power_in"))
      (node (ref "U2") (pin "AC15") (pinfunction "VSS_AC15") (pintype "power_in"))
      (node (ref "U2") (pin "AC17") (pinfunction "VSS_AC17") (pintype "power_in"))
      (node (ref "U2") (pin "AC21") (pinfunction "VSS_AC21") (pintype "power_in"))
      (node (ref "U2") (pin "AC8") (pinfunction "VSS_AC8") (pintype "power_in"))
      (node (ref "U2") (pin "AD24") (pinfunction "VSS_AD24") (pintype "power_in"))
      (node (ref "U2") (pin "AD26") (pinfunction "VSS_AD26") (pintype "power_in"))
      (node (ref "U2") (pin "AD3") (pinfunction "VSS_AD3") (pintype "power_in"))
      (node (ref "U2") (pin "AD5") (pinfunction "VSS_AD5") (pintype "power_in"))
      (node (ref "U2") (pin "AD6") (pinfunction "VSS_AD6") (pintype "power_in"))
      (node (ref "U2") (pin "AE17") (pinfunction "VSS_AE17") (pintype "power_in"))
      (node (ref "U2") (pin "AE21") (pinfunction "VSS_AE21") (pintype "power_in"))
      (node (ref "U2") (pin "AE6") (pinfunction "VSS_AE6") (pintype "power_in"))
      (node (ref "U2") (pin "AE7") (pinfunction "VSS_AE7") (pintype "power_in"))
      (node (ref "U2") (pin "AE8") (pinfunction "VSS_AE8") (pintype "power_in"))
      (node (ref "U2") (pin "AE9") (pinfunction "VSS_AE9") (pintype "power_in"))
      (node (ref "U2") (pin "AF10") (pinfunction "VSS_AF10") (pintype "power_in"))
      (node (ref "U2") (pin "AF11") (pinfunction "VSS_AF11") (pintype "power_in"))
      (node (ref "U2") (pin "AF13") (pinfunction "VSS_AF13") (pintype "power_in"))
      (node (ref "U2") (pin "AF14") (pinfunction "VSS_AF14") (pintype "power_in"))
      (node (ref "U2") (pin "AF15") (pinfunction "VSS_AF15") (pintype "power_in"))
      (node (ref "U2") (pin "AF24") (pinfunction "VSS_AF24") (pintype "power_in"))
      (node (ref "U2") (pin "AF26") (pinfunction "VSS_AF26") (pintype "power_in"))
      (node (ref "U2") (pin "AF3") (pinfunction "VSS_AF3") (pintype "power_in"))
      (node (ref "U2") (pin "AF5") (pinfunction "VSS_AF5") (pintype "power_in"))
      (node (ref "U2") (pin "AF8") (pinfunction "VSS_AF8") (pintype "power_in"))
      (node (ref "U2") (pin "AF9") (pinfunction "VSS_AF9") (pintype "power_in"))
      (node (ref "U2") (pin "AG10") (pinfunction "VSS_AG10") (pintype "power_in"))
      (node (ref "U2") (pin "AH1") (pinfunction "VSS_AH1") (pintype "power_in"))
      (node (ref "U2") (pin "AH28") (pinfunction "VSS_AH28") (pintype "power_in"))
      (node (ref "U2") (pin "B23") (pinfunction "VSS_B23") (pintype "power_in"))
      (node (ref "U2") (pin "B26") (pinfunction "VSS_B26") (pintype "power_in"))
      (node (ref "U2") (pin "B5") (pinfunction "VSS_B5") (pintype "power_in"))
      (node (ref "U2") (pin "C10") (pinfunction "VSS_C10") (pintype "power_in"))
      (node (ref "U2") (pin "C13") (pinfunction "VSS_C13") (pintype "power_in"))
      (node (ref "U2") (pin "C14") (pinfunction "VSS_C14") (pintype "power_in"))
      (node (ref "U2") (pin "C15") (pinfunction "VSS_C15") (pintype "power_in"))
      (node (ref "U2") (pin "C23") (pinfunction "VSS_C23") (pintype "power_in"))
      (node (ref "U2") (pin "C24") (pinfunction "VSS_C24") (pintype "power_in"))
      (node (ref "U2") (pin "C25") (pinfunction "VSS_C25") (pintype "power_in"))
      (node (ref "U2") (pin "C26") (pinfunction "VSS_C26") (pintype "power_in"))
      (node (ref "U2") (pin "C3") (pinfunction "VSS_C3") (pintype "power_in"))
      (node (ref "U2") (pin "C5") (pinfunction "VSS_C5") (pintype "power_in"))
      (node (ref "U2") (pin "C7") (pinfunction "VSS_C7") (pintype "power_in"))
      (node (ref "U2") (pin "D12") (pinfunction "VSS_D12") (pintype "power_in"))
      (node (ref "U2") (pin "D17") (pinfunction "VSS_D17") (pintype "power_in"))
      (node (ref "U2") (pin "D21") (pinfunction "VSS_D21") (pintype "power_in"))
      (node (ref "U2") (pin "D8") (pinfunction "VSS_D8") (pintype "power_in"))
      (node (ref "U2") (pin "E24") (pinfunction "VSS_E24") (pintype "power_in"))
      (node (ref "U2") (pin "E26") (pinfunction "VSS_E26") (pintype "power_in"))
      (node (ref "U2") (pin "E3") (pinfunction "VSS_E3") (pintype "power_in"))
      (node (ref "U2") (pin "E5") (pinfunction "VSS_E5") (pintype "power_in"))
      (node (ref "U2") (pin "F10") (pinfunction "VSS_F10") (pintype "power_in"))
      (node (ref "U2") (pin "F12") (pinfunction "VSS_F12") (pintype "power_in"))
      (node (ref "U2") (pin "F14") (pinfunction "VSS_F14") (pintype "power_in"))
      (node (ref "U2") (pin "F15") (pinfunction "VSS_F15") (pintype "power_in"))
      (node (ref "U2") (pin "F17") (pinfunction "VSS_F17") (pintype "power_in"))
      (node (ref "U2") (pin "F21") (pinfunction "VSS_F21") (pintype "power_in"))
      (node (ref "U2") (pin "F8") (pinfunction "VSS_F8") (pintype "power_in"))
      (node (ref "U2") (pin "H23") (pinfunction "VSS_H23") (pintype "power_in"))
      (node (ref "U2") (pin "H25") (pinfunction "VSS_H25") (pintype "power_in"))
      (node (ref "U2") (pin "H4") (pinfunction "VSS_H4") (pintype "power_in"))
      (node (ref "U2") (pin "H6") (pinfunction "VSS_H6") (pintype "power_in"))
      (node (ref "U2") (pin "L13") (pinfunction "VSS_L13") (pintype "power_in"))
      (node (ref "U2") (pin "L16") (pinfunction "VSS_L16") (pintype "power_in"))
      (node (ref "U2") (pin "M23") (pinfunction "VSS_M23") (pintype "power_in"))
      (node (ref "U2") (pin "M25") (pinfunction "VSS_M25") (pintype "power_in"))
      (node (ref "U2") (pin "M4") (pinfunction "VSS_M4") (pintype "power_in"))
      (node (ref "U2") (pin "M6") (pinfunction "VSS_M6") (pintype "power_in"))
      (node (ref "U2") (pin "N11") (pinfunction "VSS_N11") (pintype "power_in"))
      (node (ref "U2") (pin "N18") (pinfunction "VSS_N18") (pintype "power_in"))
      (node (ref "U2") (pin "T11") (pinfunction "VSS_T11") (pintype "power_in"))
      (node (ref "U2") (pin "T18") (pinfunction "VSS_T18") (pintype "power_in"))
      (node (ref "U2") (pin "U23") (pinfunction "VSS_U23") (pintype "power_in"))
      (node (ref "U2") (pin "U25") (pinfunction "VSS_U25") (pintype "power_in"))
      (node (ref "U2") (pin "U4") (pinfunction "VSS_U4") (pintype "power_in"))
      (node (ref "U2") (pin "U6") (pinfunction "VSS_U6") (pintype "power_in"))
      (node (ref "U2") (pin "V13") (pinfunction "VSS_V13") (pintype "power_in"))
      (node (ref "U2") (pin "V16") (pinfunction "VSS_V16") (pintype "power_in"))
      (node (ref "U2") (pin "W3") (pinfunction "VSS_W3") (pintype "power_in"))
      (node (ref "U2") (pin "W6") (pinfunction "VSS_W6") (pintype "power_in"))
    )
    (net (code "4") (name "Net-(U2A-PVCC_EPDC_LCD_CAP)") (class "Default")
      (node (ref "C79") (pin "2") (pinfunction "2_2") (pintype "passive"))
      (node (ref "U2") (pin "R20") (pinfunction "PVCC_EPDC_LCD_CAP_R20") (pintype "power_in"))
    )
    (net (code "5") (name "Net-(U2A-PVCC_GPIO_CAP)") (class "Default")
      (node (ref "C82") (pin "2") (pinfunction "2_2") (pintype "passive"))
      (node (ref "U2") (pin "AB11") (pinfunction "PVCC_GPIO_CAP_AB11") (pintype "power_in"))
    )
    (net (code "6") (name "Net-(U2A-PVCC_I2C_SPI_UART_CAP)") (class "Default")
      (node (ref "C85") (pin "2") (pinfunction "2_2") (pintype "passive"))
      (node (ref "U2") (pin "W8") (pinfunction "PVCC_I2C_SPI_UART_CAP_W8") (pintype "power_in"))
    )
    (net (code "7") (name "Net-(U2A-VDD_1P2_CAP)") (class "Default")
      (node (ref "C84") (pin "1") (pinfunction "1_1") (pintype "passive"))
      (node (ref "U2") (pin "AA10") (pinfunction "VDD_1P2_CAP_AA10") (pintype "power_in"))
    )
    (net (code "8") (name "Net-(U2B-VDDA_1P0_CAP)") (class "Default")
      (node (ref "C100") (pin "2") (pinfunction "2_2") (pintype "passive"))
      (node (ref "C99") (pin "1") (pinfunction "1_1") (pintype "passive"))
      (node (ref "U2") (pin "AH7") (pinfunction "VDDA_1P0_CAP_AH7") (pintype "power_in"))
    )
    (net (code "9") (name "Net-(U2B-VDD_LPSR_1P0_CAP)") (class "Default")
      (node (ref "C65") (pin "1") (pinfunction "1_1") (pintype "passive"))
      (node (ref "U2") (pin "AG6") (pinfunction "VDD_LPSR_1P0_CAP_AG6") (pintype "power_in"))
    )
    (net (code "10") (name "Net-(U2B-VDD_MIPI_1P0)") (class "Default")
      (node (ref "C66") (pin "2") (pinfunction "2_2") (pintype "passive"))
      (node (ref "C67") (pin "1") (pinfunction "1_1") (pintype "passive"))
      (node (ref "U2") (pin "J16") (pinfunction "VDD_MIPI_1P0_J16") (pintype "power_in"))
    )
    (net (code "11") (name "Net-(U2B-VDD_SNVS_1P8_CAP)") (class "Default")
      (node (ref "C68") (pin "2") (pinfunction "2_2") (pintype "passive"))
      (node (ref "U2") (pin "AG7") (pinfunction "VDD_SNVS_1P8_CAP_AG7") (pintype "power_in"))
    )
    (net (code "12") (name "Net-(U2B-VDD_USB_OTG1_1P0_CAP)") (class "Default")
      (node (ref "C70") (pin "1") (pinfunction "1_1") (pintype "passive"))
      (node (ref "U2") (pin "E9") (pinfunction "VDD_USB_OTG1_1P0_CAP_E9") (pintype "power_in"))
    )
    (net (code "13") (name "Net-(U2B-VDD_USB_OTG2_1P0_CAP)") (class "Default")
      (node (ref "C80") (pin "1") (pinfunction "1_1") (pintype "passive"))
      (node (ref "U2") (pin "F9") (pinfunction "VDD_USB_OTG2_1P0_CAP_F9") (pintype "power_in"))
    )
    (net (code "14") (name "PVCC SAI SD CAP") (class "Default")
      (node (ref "C73") (pin "2") (pinfunction "2_2") (pintype "passive"))
      (node (ref "U2") (pin "G16") (pinfunction "PVCC_ENET_CAP_G16") (pintype "power_in"))
      (node (ref "U2") (pin "J14") (pinfunction "PVCC_SAI_SD_CAP_J14") (pintype "bidirectional"))
    )
    (net (code "15") (name "USB_OTG1_3P3_IN") (class "Default")
      (node (ref "C101") (pin "1") (pinfunction "1_1") (pintype "passive"))
      (node (ref "C104") (pin "1") (pinfunction "1_1") (pintype "passive"))
      (node (ref "C105") (pin "1") (pinfunction "1_1") (pintype "passive"))
      (node (ref "C106") (pin "2") (pinfunction "2_2") (pintype "passive"))
      (node (ref "C107") (pin "2") (pinfunction "2_2") (pintype "passive"))
      (node (ref "C110") (pin "1") (pinfunction "1_1") (pintype "passive"))
      (node (ref "C111") (pin "2") (pinfunction "2_2") (pintype "passive"))
      (node (ref "C112") (pin "1") (pinfunction "1_1") (pintype "passive"))
      (node (ref "C113") (pin "1") (pinfunction "1_1") (pintype "passive"))
      (node (ref "C114") (pin "1") (pinfunction "1_1") (pintype "passive"))
      (node (ref "C115") (pin "1") (pinfunction "1_1") (pintype "passive"))
      (node (ref "C69") (pin "2") (pinfunction "2_2") (pintype "passive"))
      (node (ref "C71") (pin "1") (pinfunction "1_1") (pintype "passive"))
      (node (ref "C72") (pin "1") (pinfunction "1_1") (pintype "passive"))
      (node (ref "C81") (pin "1") (pinfunction "1_1") (pintype "passive"))
      (node (ref "C83") (pin "2") (pinfunction "2_2") (pintype "passive"))
      (node (ref "C92") (pin "1") (pinfunction "1_1") (pintype "passive"))
      (node (ref "C93") (pin "2") (pinfunction "2_2") (pintype "passive"))
      (node (ref "U2") (pin "D11") (pinfunction "VDD_USB_OTG2_3P3_IN_D11") (pintype "power_in"))
      (node (ref "U2") (pin "D9") (pinfunction "VDD_USB_OTG1_3P3_IN_D9") (pintype "power_in"))
      (node (ref "U2") (pin "J11") (pinfunction "NVCC_SD1_J11") (pintype "power_in"))
      (node (ref "U2") (pin "J13") (pinfunction "NVCC_SAI_J13") (pintype "power_in"))
      (node (ref "U2") (pin "J18") (pinfunction "NVCC_ENET1_J18") (pintype "power_in"))
      (node (ref "U2") (pin "L20") (pinfunction "NVCC_LCD_L20") (pintype "power_in"))
      (node (ref "U2") (pin "L9") (pinfunction "NVCC_SD2_L9") (pintype "power_in"))
      (node (ref "U2") (pin "N20") (pinfunction "NVCC_EPDC2_N20") (pintype "power_in"))
      (node (ref "U2") (pin "N9") (pinfunction "NVCC_SD3_N9") (pintype "power_in"))
      (node (ref "U2") (pin "P20") (pinfunction "NVCC_EPDC1_P20") (pintype "power_in"))
      (node (ref "U2") (pin "P9") (pinfunction "NVCC_SPI_P9") (pintype "power_in"))
      (node (ref "U2") (pin "R9") (pinfunction "NVCC_I2C_R9") (pintype "power_in"))
      (node (ref "U2") (pin "T9") (pinfunction "NVCC_UART_T9") (pintype "power_in"))
      (node (ref "U2") (pin "Y11") (pinfunction "NVCC_GPIO2_Y11") (pintype "power_in"))
      (node (ref "U2") (pin "Y13") (pinfunction "VDD_SNVS_IN_Y13") (pintype "power_in"))
      (node (ref "U2") (pin "Y9") (pinfunction "NVCC_GPIO1_Y9") (pintype "power_in"))
    )
    (net (code "16") (name "unconnected-(U2B-VDD_USB_H_1P2-PadC12)") (class "Default")
      (node (ref "U2") (pin "C12") (pinfunction "VDD_USB_H_1P2_C12") (pintype "power_in"))
    )
    (net (code "17") (name "unconnected-(U2B-VDD_USB_H_1P2-PadG13)") (class "Default")
      (node (ref "U2") (pin "G13") (pinfunction "VDD_USB_H_1P2_G13") (pintype "power_in"))
    )
  )
)
